# Hi_Current.net
KiCad netlist of a schematic drawn in Altium Designer
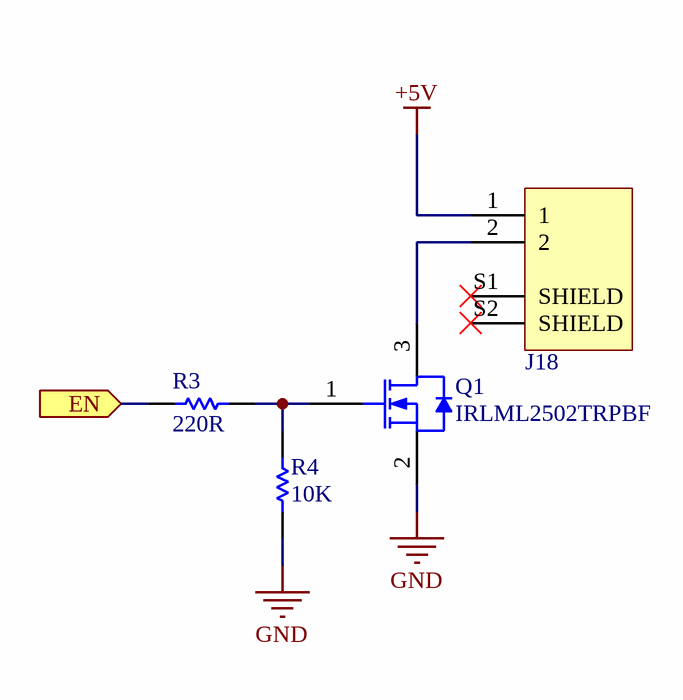
[diagram p0: Hi_Current.SchDoc]

(export (version "E")
  (design (tool "Eeschema 10.0.6"))
  (components
    (comp (ref "J18")
      (value "2 pin vertical JST GH")
      (footprint "JST_BM02B-GHS-TBT(LF)(SN)(N)")
      (description "JST GH vertical 2 pin\r\nDigiKey part no. 455-1578-1-ND")
      (fields (field (name "MF") "JST Sales") (field (name "DIGI-KEY_PART_NUMBER") "455-1580-1-ND"))
      (libsource (lib "Moonlight_Components") (part "BM02B-GHS-TBT(LF)(SN)(N)"))
    )
    (comp (ref "Q1")
      (value "IRLML2502TRPBF")
      (footprint "INTR-SOT-23-3_V")
      (description "N-Channel HEXFET(R) Power MOSFET, 20 V VDS, +/- 12 V VGS, 4.2 A, 3-Pin SOT23, RoHS, Tape and Reel")
      (fields (field (name "MANUFACTURER") "International Rectifier"))
      (libsource (lib "Moonlight_Components") (part "IRLML2502TRPBF"))
    )
    (comp (ref "R3")
      (value "220R")
      (footprint "0603_RES")
      (libsource (lib "Moonlight-Components") (part "Resistor"))
    )
    (comp (ref "R4")
      (value "10K")
      (footprint "0603_RES")
      (libsource (lib "Moonlight-Components") (part "Resistor"))
    )
  )
  (nets
    (net (code "1") (name "+5V") (class "Default")
      (node (ref "J18") (pin "1") (pinfunction "1_1") (pintype "passive"))
    )
    (net (code "2") (name "/EN") (class "Default")
      (node (ref "R3") (pin "1") (pinfunction "1_1") (pintype "passive"))
    )
    (net (code "3") (name "GND") (class "Default")
      (node (ref "Q1") (pin "2") (pinfunction "S_2") (pintype "passive"))
      (node (ref "R4") (pin "2") (pinfunction "2_2") (pintype "passive"))
    )
    (net (code "4") (name "Net-(Q1-D)") (class "Default")
      (node (ref "J18") (pin "2") (pinfunction "2_2") (pintype "passive"))
      (node (ref "Q1") (pin "3") (pinfunction "D_3") (pintype "passive"))
    )
    (net (code "5") (name "Net-(Q1-G)") (class "Default")
      (node (ref "Q1") (pin "1") (pinfunction "G_1") (pintype "passive"))
      (node (ref "R3") (pin "2") (pinfunction "2_2") (pintype "passive"))
      (node (ref "R4") (pin "1") (pinfunction "1_1") (pintype "passive"))
    )
    (net (code "6") (name "unconnected-(J18-SHIELD-PadS1)") (class "Default")
      (node (ref "J18") (pin "S1") (pinfunction "SHIELD_S1") (pintype "passive+no_connect"))
    )
    (net (code "7") (name "unconnected-(J18-SHIELD-PadS2)") (class "Default")
      (node (ref "J18") (pin "S2") (pinfunction "SHIELD_S2") (pintype "passive+no_connect"))
    )
  )
)
